# EC544.net
KiCad netlist of a schematic drawn in EAGLE
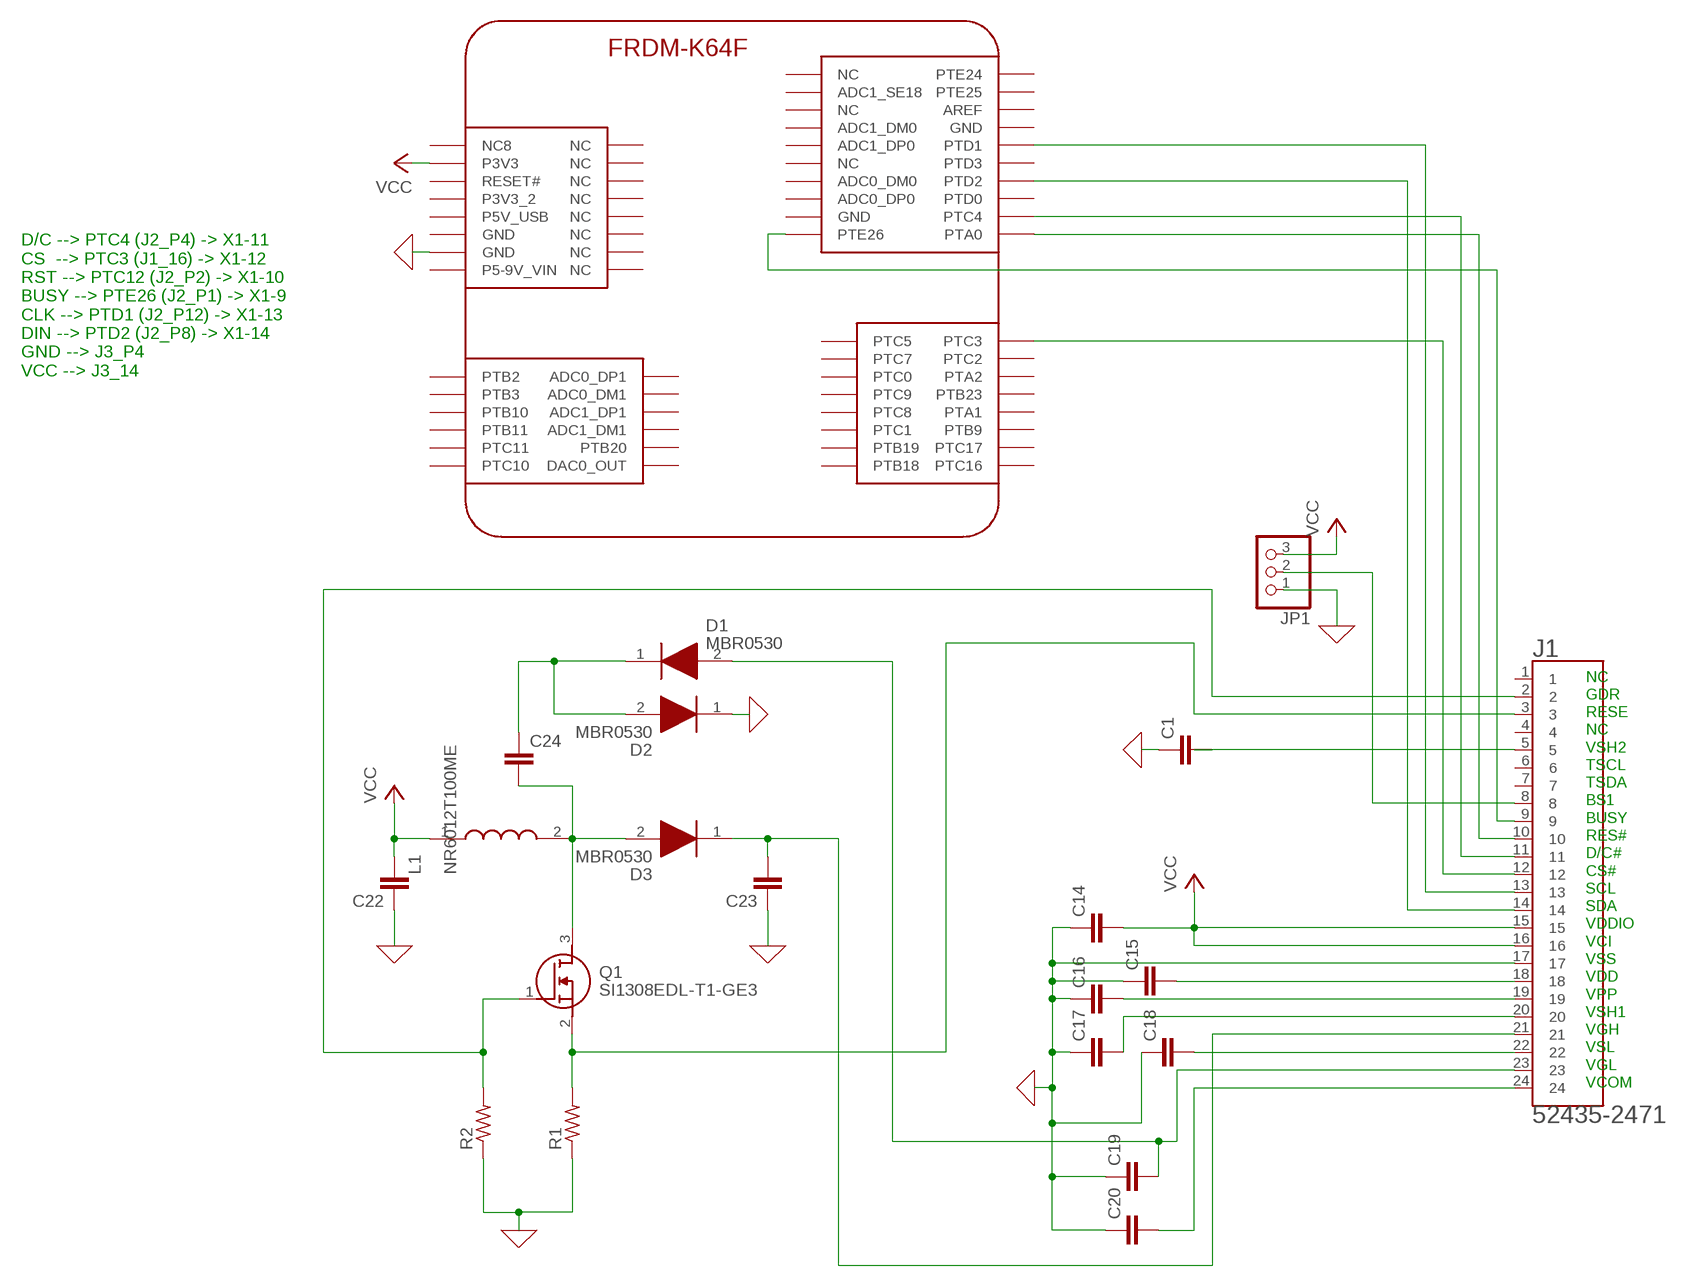
[diagram p0: schematic, sheet 1]

(export (version "E")
  (design (tool "Eeschema 10.0.6"))
  (components
    (comp (ref "C1")
      (value "C-EUC0805")
      (footprint "eagle-import:C0805")
      (libsource (lib "eagle-import") (part "C-EUC0805"))
    )
    (comp (ref "C14")
      (value "C-EUC0805")
      (footprint "eagle-import:C0805")
      (libsource (lib "eagle-import") (part "C-EUC0805"))
    )
    (comp (ref "C15")
      (value "C-EUC0805")
      (footprint "eagle-import:C0805")
      (libsource (lib "eagle-import") (part "C-EUC0805"))
    )
    (comp (ref "C16")
      (value "C-EUC0805")
      (footprint "eagle-import:C0805")
      (libsource (lib "eagle-import") (part "C-EUC0805"))
    )
    (comp (ref "C17")
      (value "C-EUC0805")
      (footprint "eagle-import:C0805")
      (libsource (lib "eagle-import") (part "C-EUC0805"))
    )
    (comp (ref "C18")
      (value "C-EUC0805")
      (footprint "eagle-import:C0805")
      (libsource (lib "eagle-import") (part "C-EUC0805"))
    )
    (comp (ref "C19")
      (value "C-EUC0805")
      (footprint "eagle-import:C0805")
      (libsource (lib "eagle-import") (part "C-EUC0805"))
    )
    (comp (ref "C20")
      (value "C-EUC0805")
      (footprint "eagle-import:C0805")
      (libsource (lib "eagle-import") (part "C-EUC0805"))
    )
    (comp (ref "C22")
      (value "C-EUC0805")
      (footprint "eagle-import:C0805")
      (libsource (lib "eagle-import") (part "C-EUC0805"))
    )
    (comp (ref "C23")
      (value "C-EUC0805")
      (footprint "eagle-import:C0805")
      (libsource (lib "eagle-import") (part "C-EUC0805"))
    )
    (comp (ref "C24")
      (value "C-EUC0805")
      (footprint "eagle-import:C0805")
      (libsource (lib "eagle-import") (part "C-EUC0805"))
    )
    (comp (ref "D1")
      (value "MBR0530")
      (footprint "eagle-import:SOD3716X135N")
      (fields (field (name "MOUSER_PART_NUMBER") "512-MBR0530"))
      (libsource (lib "eagle-import") (part "MBR0530"))
    )
    (comp (ref "D2")
      (value "MBR0530")
      (footprint "eagle-import:SOD3716X135N")
      (fields (field (name "MOUSER_PART_NUMBER") "512-MBR0530"))
      (libsource (lib "eagle-import") (part "MBR0530"))
    )
    (comp (ref "D3")
      (value "MBR0530")
      (footprint "eagle-import:SOD3716X135N")
      (fields (field (name "MOUSER_PART_NUMBER") "512-MBR0530"))
      (libsource (lib "eagle-import") (part "MBR0530"))
    )
    (comp (ref "FRDM1")
      (value "FRDM-K64FNORMAL")
      (footprint "eagle-import:FRDM_K64F")
      (libsource (lib "eagle-import") (part "FRDM-K64FNORMAL"))
    )
    (comp (ref "J1")
      (value "52435-2471")
      (footprint "eagle-import:MOLEX_52435-2471")
      (fields (field (name "MF") "Molex"))
      (libsource (lib "eagle-import") (part "52435-2471"))
    )
    (comp (ref "JP1")
      (value "PINHD-1X3")
      (footprint "eagle-import:1X03")
      (libsource (lib "eagle-import") (part "PINHD-1X3"))
    )
    (comp (ref "L1")
      (value "NR6012T100ME")
      (footprint "eagle-import:NR6012T100ME")
      (fields (field (name "MOUSER_PART_NUMBER") "963-NR6012T100ME"))
      (libsource (lib "eagle-import") (part "NR6012T100ME"))
    )
    (comp (ref "Q1")
      (value "SI1308EDL-T1-GE3")
      (footprint "eagle-import:SOT65P210X110-3N")
      (fields
        (field (name "MANUFACTURER_PART_NUMBER") "Si1308EDL-T1-GE3")
        (field (name "MOUSER_PART_NUMBER") "78-SI1308EDL-T1-GE3")
      )
      (libsource (lib "eagle-import") (part "SI1308EDL-T1-GE3"))
    )
    (comp (ref "R1")
      (value "R-US_0204/5")
      (footprint "eagle-import:0204_5")
      (libsource (lib "eagle-import") (part "R-US_0204/5"))
    )
    (comp (ref "R2")
      (value "R-US_0204/5")
      (footprint "eagle-import:0204_5")
      (libsource (lib "eagle-import") (part "R-US_0204/5"))
    )
  )
  (nets
    (net (code "1") (name "GND") (class "Default")
      (node (ref "C1") (pin "1") (pinfunction "1_1") (pintype "passive"))
      (node (ref "C14") (pin "1") (pinfunction "1_1") (pintype "passive"))
      (node (ref "C15") (pin "1") (pinfunction "1_1") (pintype "passive"))
      (node (ref "C16") (pin "1") (pinfunction "1_1") (pintype "passive"))
      (node (ref "C17") (pin "1") (pinfunction "1_1") (pintype "passive"))
      (node (ref "C18") (pin "1") (pinfunction "1_1") (pintype "passive"))
      (node (ref "C19") (pin "1") (pinfunction "1_1") (pintype "passive"))
      (node (ref "C20") (pin "1") (pinfunction "1_1") (pintype "passive"))
      (node (ref "C22") (pin "1") (pinfunction "1_1") (pintype "passive"))
      (node (ref "C23") (pin "1") (pinfunction "1_1") (pintype "passive"))
      (node (ref "D2") (pin "1") (pinfunction "K_1") (pintype "bidirectional"))
      (node (ref "FRDM1") (pin "J3.14") (pinfunction "GND_J3.14") (pintype "bidirectional"))
      (node (ref "J1") (pin "17") (pinfunction "17_17") (pintype "passive"))
      (node (ref "JP1") (pin "1") (pinfunction "1_1") (pintype "passive"))
      (node (ref "R1") (pin "1") (pinfunction "1_1") (pintype "passive"))
      (node (ref "R2") (pin "1") (pinfunction "1_1") (pintype "passive"))
    )
    (net (code "2") (name "Net-(C1-Pad2)") (class "Default")
      (node (ref "C1") (pin "2") (pinfunction "2_2") (pintype "passive"))
      (node (ref "J1") (pin "5") (pinfunction "5_5") (pintype "passive"))
    )
    (net (code "3") (name "Net-(C15-Pad2)") (class "Default")
      (node (ref "C15") (pin "2") (pinfunction "2_2") (pintype "passive"))
      (node (ref "J1") (pin "18") (pinfunction "18_18") (pintype "passive"))
    )
    (net (code "4") (name "Net-(C16-Pad2)") (class "Default")
      (node (ref "C16") (pin "2") (pinfunction "2_2") (pintype "passive"))
      (node (ref "J1") (pin "19") (pinfunction "19_19") (pintype "passive"))
    )
    (net (code "5") (name "Net-(C17-Pad2)") (class "Default")
      (node (ref "C17") (pin "2") (pinfunction "2_2") (pintype "passive"))
      (node (ref "J1") (pin "20") (pinfunction "20_20") (pintype "passive"))
    )
    (net (code "6") (name "Net-(C18-Pad2)") (class "Default")
      (node (ref "C18") (pin "2") (pinfunction "2_2") (pintype "passive"))
      (node (ref "J1") (pin "22") (pinfunction "22_22") (pintype "passive"))
    )
    (net (code "7") (name "Net-(C20-Pad2)") (class "Default")
      (node (ref "C20") (pin "2") (pinfunction "2_2") (pintype "passive"))
      (node (ref "J1") (pin "24") (pinfunction "24_24") (pintype "passive"))
    )
    (net (code "8") (name "Net-(D1-A)") (class "Default")
      (node (ref "C19") (pin "2") (pinfunction "2_2") (pintype "passive"))
      (node (ref "D1") (pin "2") (pinfunction "A_2") (pintype "bidirectional"))
      (node (ref "J1") (pin "23") (pinfunction "23_23") (pintype "passive"))
    )
    (net (code "9") (name "Net-(D1-K)") (class "Default")
      (node (ref "C24") (pin "1") (pinfunction "1_1") (pintype "passive"))
      (node (ref "D1") (pin "1") (pinfunction "K_1") (pintype "bidirectional"))
      (node (ref "D2") (pin "2") (pinfunction "A_2") (pintype "bidirectional"))
    )
    (net (code "10") (name "Net-(D3-A)") (class "Default")
      (node (ref "C24") (pin "2") (pinfunction "2_2") (pintype "passive"))
      (node (ref "D3") (pin "2") (pinfunction "A_2") (pintype "bidirectional"))
      (node (ref "L1") (pin "2") (pinfunction "2_2") (pintype "bidirectional"))
      (node (ref "Q1") (pin "3") (pinfunction "D_3") (pintype "bidirectional"))
    )
    (net (code "11") (name "Net-(D3-K)") (class "Default")
      (node (ref "C23") (pin "2") (pinfunction "2_2") (pintype "passive"))
      (node (ref "D3") (pin "1") (pinfunction "K_1") (pintype "bidirectional"))
      (node (ref "J1") (pin "21") (pinfunction "21_21") (pintype "passive"))
    )
    (net (code "12") (name "Net-(FRDM1-PTA0)") (class "Default")
      (node (ref "FRDM1") (pin "J2.2") (pinfunction "PTA0_J2.2") (pintype "bidirectional"))
      (node (ref "J1") (pin "10") (pinfunction "10_10") (pintype "passive"))
    )
    (net (code "13") (name "Net-(FRDM1-PTC3)") (class "Default")
      (node (ref "FRDM1") (pin "J1.16") (pinfunction "PTC3_J1.16") (pintype "bidirectional"))
      (node (ref "J1") (pin "12") (pinfunction "12_12") (pintype "passive"))
    )
    (net (code "14") (name "Net-(FRDM1-PTC4)") (class "Default")
      (node (ref "FRDM1") (pin "J2.4") (pinfunction "PTC4_J2.4") (pintype "bidirectional"))
      (node (ref "J1") (pin "11") (pinfunction "11_11") (pintype "passive"))
    )
    (net (code "15") (name "Net-(FRDM1-PTD1)") (class "Default")
      (node (ref "FRDM1") (pin "J2.12") (pinfunction "PTD1_J2.12") (pintype "bidirectional"))
      (node (ref "J1") (pin "13") (pinfunction "13_13") (pintype "passive"))
    )
    (net (code "16") (name "Net-(FRDM1-PTD2)") (class "Default")
      (node (ref "FRDM1") (pin "J2.8") (pinfunction "PTD2_J2.8") (pintype "bidirectional"))
      (node (ref "J1") (pin "14") (pinfunction "14_14") (pintype "passive"))
    )
    (net (code "17") (name "Net-(FRDM1-PTE26)") (class "Default")
      (node (ref "FRDM1") (pin "J2.1") (pinfunction "PTE26_J2.1") (pintype "bidirectional"))
      (node (ref "J1") (pin "9") (pinfunction "9_9") (pintype "passive"))
    )
    (net (code "18") (name "Net-(J1-Pad8)") (class "Default")
      (node (ref "J1") (pin "8") (pinfunction "8_8") (pintype "passive"))
      (node (ref "JP1") (pin "2") (pinfunction "2_2") (pintype "passive"))
    )
    (net (code "19") (name "Net-(Q1-G)") (class "Default")
      (node (ref "J1") (pin "2") (pinfunction "2_2") (pintype "passive"))
      (node (ref "Q1") (pin "1") (pinfunction "G_1") (pintype "bidirectional"))
      (node (ref "R2") (pin "2") (pinfunction "2_2") (pintype "passive"))
    )
    (net (code "20") (name "Net-(Q1-S)") (class "Default")
      (node (ref "J1") (pin "3") (pinfunction "3_3") (pintype "passive"))
      (node (ref "Q1") (pin "2") (pinfunction "S_2") (pintype "bidirectional"))
      (node (ref "R1") (pin "2") (pinfunction "2_2") (pintype "passive"))
    )
    (net (code "21") (name "VCC") (class "Default")
      (node (ref "C14") (pin "2") (pinfunction "2_2") (pintype "passive"))
      (node (ref "C22") (pin "2") (pinfunction "2_2") (pintype "passive"))
      (node (ref "FRDM1") (pin "J3.4") (pinfunction "P3V3_J3.4") (pintype "bidirectional"))
      (node (ref "J1") (pin "15") (pinfunction "15_15") (pintype "passive"))
      (node (ref "J1") (pin "16") (pinfunction "16_16") (pintype "passive"))
      (node (ref "JP1") (pin "3") (pinfunction "3_3") (pintype "passive"))
      (node (ref "L1") (pin "1") (pinfunction "1_1") (pintype "bidirectional"))
    )
    (net (code "22") (name "unconnected-(FRDM1-ADC0_DM0-PadJ2.7)") (class "Default")
      (node (ref "FRDM1") (pin "J2.7") (pinfunction "ADC0_DM0_J2.7") (pintype "bidirectional"))
    )
    (net (code "23") (name "unconnected-(FRDM1-ADC0_DM1-PadJ4.3)") (class "Default")
      (node (ref "FRDM1") (pin "J4.3") (pinfunction "ADC0_DM1_J4.3") (pintype "bidirectional"))
    )
    (net (code "24") (name "unconnected-(FRDM1-ADC0_DP0-PadJ2.5)") (class "Default")
      (node (ref "FRDM1") (pin "J2.5") (pinfunction "ADC0_DP0_J2.5") (pintype "bidirectional"))
    )
    (net (code "25") (name "unconnected-(FRDM1-ADC0_DP1-PadJ4.1)") (class "Default")
      (node (ref "FRDM1") (pin "J4.1") (pinfunction "ADC0_DP1_J4.1") (pintype "bidirectional"))
    )
    (net (code "26") (name "unconnected-(FRDM1-ADC1_DM0-PadJ2.13)") (class "Default")
      (node (ref "FRDM1") (pin "J2.13") (pinfunction "ADC1_DM0_J2.13") (pintype "bidirectional"))
    )
    (net (code "27") (name "unconnected-(FRDM1-ADC1_DM1-PadJ4.7)") (class "Default")
      (node (ref "FRDM1") (pin "J4.7") (pinfunction "ADC1_DM1_J4.7") (pintype "bidirectional"))
    )
    (net (code "28") (name "unconnected-(FRDM1-ADC1_DP0-PadJ2.11)") (class "Default")
      (node (ref "FRDM1") (pin "J2.11") (pinfunction "ADC1_DP0_J2.11") (pintype "bidirectional"))
    )
    (net (code "29") (name "unconnected-(FRDM1-ADC1_DP1-PadJ4.5)") (class "Default")
      (node (ref "FRDM1") (pin "J4.5") (pinfunction "ADC1_DP1_J4.5") (pintype "bidirectional"))
    )
    (net (code "30") (name "unconnected-(FRDM1-ADC1_SE18-PadJ2.17)") (class "Default")
      (node (ref "FRDM1") (pin "J2.17") (pinfunction "ADC1_SE18_J2.17") (pintype "bidirectional"))
    )
    (net (code "31") (name "unconnected-(FRDM1-AREF-PadJ2.16)") (class "Default")
      (node (ref "FRDM1") (pin "J2.16") (pinfunction "AREF_J2.16") (pintype "bidirectional"))
    )
    (net (code "32") (name "unconnected-(FRDM1-DAC0_OUT-PadJ4.11)") (class "Default")
      (node (ref "FRDM1") (pin "J4.11") (pinfunction "DAC0_OUT_J4.11") (pintype "bidirectional"))
    )
    (net (code "33") (name "unconnected-(FRDM1-GND-PadJ2.3)") (class "Default")
      (node (ref "FRDM1") (pin "J2.3") (pinfunction "GND_J2.3") (pintype "bidirectional"))
    )
    (net (code "34") (name "unconnected-(FRDM1-GND-PadJ2.14)") (class "Default")
      (node (ref "FRDM1") (pin "J2.14") (pinfunction "GND_J2.14") (pintype "bidirectional"))
    )
    (net (code "35") (name "unconnected-(FRDM1-GND-PadJ3.12)") (class "Default")
      (node (ref "FRDM1") (pin "J3.12") (pinfunction "GND_J3.12") (pintype "bidirectional"))
    )
    (net (code "36") (name "unconnected-(FRDM1-NC-PadJ2.9)") (class "Default")
      (node (ref "FRDM1") (pin "J2.9") (pinfunction "NC_J2.9") (pintype "bidirectional"))
    )
    (net (code "37") (name "unconnected-(FRDM1-NC-PadJ2.15)") (class "Default")
      (node (ref "FRDM1") (pin "J2.15") (pinfunction "NC_J2.15") (pintype "bidirectional"))
    )
    (net (code "38") (name "unconnected-(FRDM1-NC-PadJ2.19)") (class "Default")
      (node (ref "FRDM1") (pin "J2.19") (pinfunction "NC_J2.19") (pintype "bidirectional"))
    )
    (net (code "39") (name "unconnected-(FRDM1-NC-PadJ3.1)") (class "Default")
      (node (ref "FRDM1") (pin "J3.1") (pinfunction "NC_J3.1") (pintype "bidirectional"))
    )
    (net (code "40") (name "unconnected-(FRDM1-NC-PadJ3.2)") (class "Default")
      (node (ref "FRDM1") (pin "J3.2") (pinfunction "NC_J3.2") (pintype "bidirectional"))
    )
    (net (code "41") (name "unconnected-(FRDM1-NC-PadJ3.3)") (class "Default")
      (node (ref "FRDM1") (pin "J3.3") (pinfunction "NC_J3.3") (pintype "bidirectional"))
    )
    (net (code "42") (name "unconnected-(FRDM1-NC-PadJ3.5)") (class "Default")
      (node (ref "FRDM1") (pin "J3.5") (pinfunction "NC_J3.5") (pintype "bidirectional"))
    )
    (net (code "43") (name "unconnected-(FRDM1-NC-PadJ3.7)") (class "Default")
      (node (ref "FRDM1") (pin "J3.7") (pinfunction "NC_J3.7") (pintype "bidirectional"))
    )
    (net (code "44") (name "unconnected-(FRDM1-NC-PadJ3.9)") (class "Default")
      (node (ref "FRDM1") (pin "J3.9") (pinfunction "NC_J3.9") (pintype "bidirectional"))
    )
    (net (code "45") (name "unconnected-(FRDM1-NC-PadJ3.11)") (class "Default")
      (node (ref "FRDM1") (pin "J3.11") (pinfunction "NC_J3.11") (pintype "bidirectional"))
    )
    (net (code "46") (name "unconnected-(FRDM1-NC-PadJ3.13)") (class "Default")
      (node (ref "FRDM1") (pin "J3.13") (pinfunction "NC_J3.13") (pintype "bidirectional"))
    )
    (net (code "47") (name "unconnected-(FRDM1-NC8-PadJ3.15)") (class "Default")
      (node (ref "FRDM1") (pin "J3.15") (pinfunction "NC8_J3.15") (pintype "bidirectional"))
    )
    (net (code "48") (name "unconnected-(FRDM1-P3V3_2-PadJ3.8)") (class "Default")
      (node (ref "FRDM1") (pin "J3.8") (pinfunction "P3V3_2_J3.8") (pintype "bidirectional"))
    )
    (net (code "49") (name "unconnected-(FRDM1-P5-9V_VIN-PadJ3.16)") (class "Default")
      (node (ref "FRDM1") (pin "J3.16") (pinfunction "P5-9V_VIN_J3.16") (pintype "bidirectional"))
    )
    (net (code "50") (name "unconnected-(FRDM1-P5V_USB-PadJ3.10)") (class "Default")
      (node (ref "FRDM1") (pin "J3.10") (pinfunction "P5V_USB_J3.10") (pintype "bidirectional"))
    )
    (net (code "51") (name "unconnected-(FRDM1-PTA1-PadJ1.8)") (class "Default")
      (node (ref "FRDM1") (pin "J1.8") (pinfunction "PTA1_J1.8") (pintype "bidirectional"))
    )
    (net (code "52") (name "unconnected-(FRDM1-PTA2-PadJ1.12)") (class "Default")
      (node (ref "FRDM1") (pin "J1.12") (pinfunction "PTA2_J1.12") (pintype "bidirectional"))
    )
    (net (code "53") (name "unconnected-(FRDM1-PTB2-PadJ4.2)") (class "Default")
      (node (ref "FRDM1") (pin "J4.2") (pinfunction "PTB2_J4.2") (pintype "bidirectional"))
    )
    (net (code "54") (name "unconnected-(FRDM1-PTB3-PadJ4.4)") (class "Default")
      (node (ref "FRDM1") (pin "J4.4") (pinfunction "PTB3_J4.4") (pintype "bidirectional"))
    )
    (net (code "55") (name "unconnected-(FRDM1-PTB9-PadJ1.6)") (class "Default")
      (node (ref "FRDM1") (pin "J1.6") (pinfunction "PTB9_J1.6") (pintype "bidirectional"))
    )
    (net (code "56") (name "unconnected-(FRDM1-PTB10-PadJ4.6)") (class "Default")
      (node (ref "FRDM1") (pin "J4.6") (pinfunction "PTB10_J4.6") (pintype "bidirectional"))
    )
    (net (code "57") (name "unconnected-(FRDM1-PTB11-PadJ4.8)") (class "Default")
      (node (ref "FRDM1") (pin "J4.8") (pinfunction "PTB11_J4.8") (pintype "bidirectional"))
    )
    (net (code "58") (name "unconnected-(FRDM1-PTB18-PadJ1.1)") (class "Default")
      (node (ref "FRDM1") (pin "J1.1") (pinfunction "PTB18_J1.1") (pintype "bidirectional"))
    )
    (net (code "59") (name "unconnected-(FRDM1-PTB19-PadJ1.3)") (class "Default")
      (node (ref "FRDM1") (pin "J1.3") (pinfunction "PTB19_J1.3") (pintype "bidirectional"))
    )
    (net (code "60") (name "unconnected-(FRDM1-PTB20-PadJ4.9)") (class "Default")
      (node (ref "FRDM1") (pin "J4.9") (pinfunction "PTB20_J4.9") (pintype "bidirectional"))
    )
    (net (code "61") (name "unconnected-(FRDM1-PTB23-PadJ1.10)") (class "Default")
      (node (ref "FRDM1") (pin "J1.10") (pinfunction "PTB23_J1.10") (pintype "bidirectional"))
    )
    (net (code "62") (name "unconnected-(FRDM1-PTC0-PadJ1.11)") (class "Default")
      (node (ref "FRDM1") (pin "J1.11") (pinfunction "PTC0_J1.11") (pintype "bidirectional"))
    )
    (net (code "63") (name "unconnected-(FRDM1-PTC1-PadJ1.5)") (class "Default")
      (node (ref "FRDM1") (pin "J1.5") (pinfunction "PTC1_J1.5") (pintype "bidirectional"))
    )
    (net (code "64") (name "unconnected-(FRDM1-PTC2-PadJ1.14)") (class "Default")
      (node (ref "FRDM1") (pin "J1.14") (pinfunction "PTC2_J1.14") (pintype "bidirectional"))
    )
    (net (code "65") (name "unconnected-(FRDM1-PTC5-PadJ1.15)") (class "Default")
      (node (ref "FRDM1") (pin "J1.15") (pinfunction "PTC5_J1.15") (pintype "bidirectional"))
    )
    (net (code "66") (name "unconnected-(FRDM1-PTC7-PadJ1.13)") (class "Default")
      (node (ref "FRDM1") (pin "J1.13") (pinfunction "PTC7_J1.13") (pintype "bidirectional"))
    )
    (net (code "67") (name "unconnected-(FRDM1-PTC8-PadJ1.7)") (class "Default")
      (node (ref "FRDM1") (pin "J1.7") (pinfunction "PTC8_J1.7") (pintype "bidirectional"))
    )
    (net (code "68") (name "unconnected-(FRDM1-PTC9-PadJ1.9)") (class "Default")
      (node (ref "FRDM1") (pin "J1.9") (pinfunction "PTC9_J1.9") (pintype "bidirectional"))
    )
    (net (code "69") (name "unconnected-(FRDM1-PTC10-PadJ4.12)") (class "Default")
      (node (ref "FRDM1") (pin "J4.12") (pinfunction "PTC10_J4.12") (pintype "bidirectional"))
    )
    (net (code "70") (name "unconnected-(FRDM1-PTC11-PadJ4.10)") (class "Default")
      (node (ref "FRDM1") (pin "J4.10") (pinfunction "PTC11_J4.10") (pintype "bidirectional"))
    )
    (net (code "71") (name "unconnected-(FRDM1-PTC16-PadJ1.2)") (class "Default")
      (node (ref "FRDM1") (pin "J1.2") (pinfunction "PTC16_J1.2") (pintype "bidirectional"))
    )
    (net (code "72") (name "unconnected-(FRDM1-PTC17-PadJ1.4)") (class "Default")
      (node (ref "FRDM1") (pin "J1.4") (pinfunction "PTC17_J1.4") (pintype "bidirectional"))
    )
    (net (code "73") (name "unconnected-(FRDM1-PTD0-PadJ2.6)") (class "Default")
      (node (ref "FRDM1") (pin "J2.6") (pinfunction "PTD0_J2.6") (pintype "bidirectional"))
    )
    (net (code "74") (name "unconnected-(FRDM1-PTD3-PadJ2.10)") (class "Default")
      (node (ref "FRDM1") (pin "J2.10") (pinfunction "PTD3_J2.10") (pintype "bidirectional"))
    )
    (net (code "75") (name "unconnected-(FRDM1-PTE24-PadJ2.20)") (class "Default")
      (node (ref "FRDM1") (pin "J2.20") (pinfunction "PTE24_J2.20") (pintype "bidirectional"))
    )
    (net (code "76") (name "unconnected-(FRDM1-PTE25-PadJ2.18)") (class "Default")
      (node (ref "FRDM1") (pin "J2.18") (pinfunction "PTE25_J2.18") (pintype "bidirectional"))
    )
    (net (code "77") (name "unconnected-(FRDM1-RESET#-PadJ3.6)") (class "Default")
      (node (ref "FRDM1") (pin "J3.6") (pinfunction "RESET#_J3.6") (pintype "bidirectional"))
    )
    (net (code "78") (name "unconnected-(J1-Pad1)") (class "Default")
      (node (ref "J1") (pin "1") (pinfunction "1_1") (pintype "passive"))
    )
    (net (code "79") (name "unconnected-(J1-Pad4)") (class "Default")
      (node (ref "J1") (pin "4") (pinfunction "4_4") (pintype "passive"))
    )
    (net (code "80") (name "unconnected-(J1-Pad6)") (class "Default")
      (node (ref "J1") (pin "6") (pinfunction "6_6") (pintype "passive"))
    )
    (net (code "81") (name "unconnected-(J1-Pad7)") (class "Default")
      (node (ref "J1") (pin "7") (pinfunction "7_7") (pintype "passive"))
    )
  )
)
